# MasterSheet.net
KiCad netlist of a schematic drawn in Altium Designer
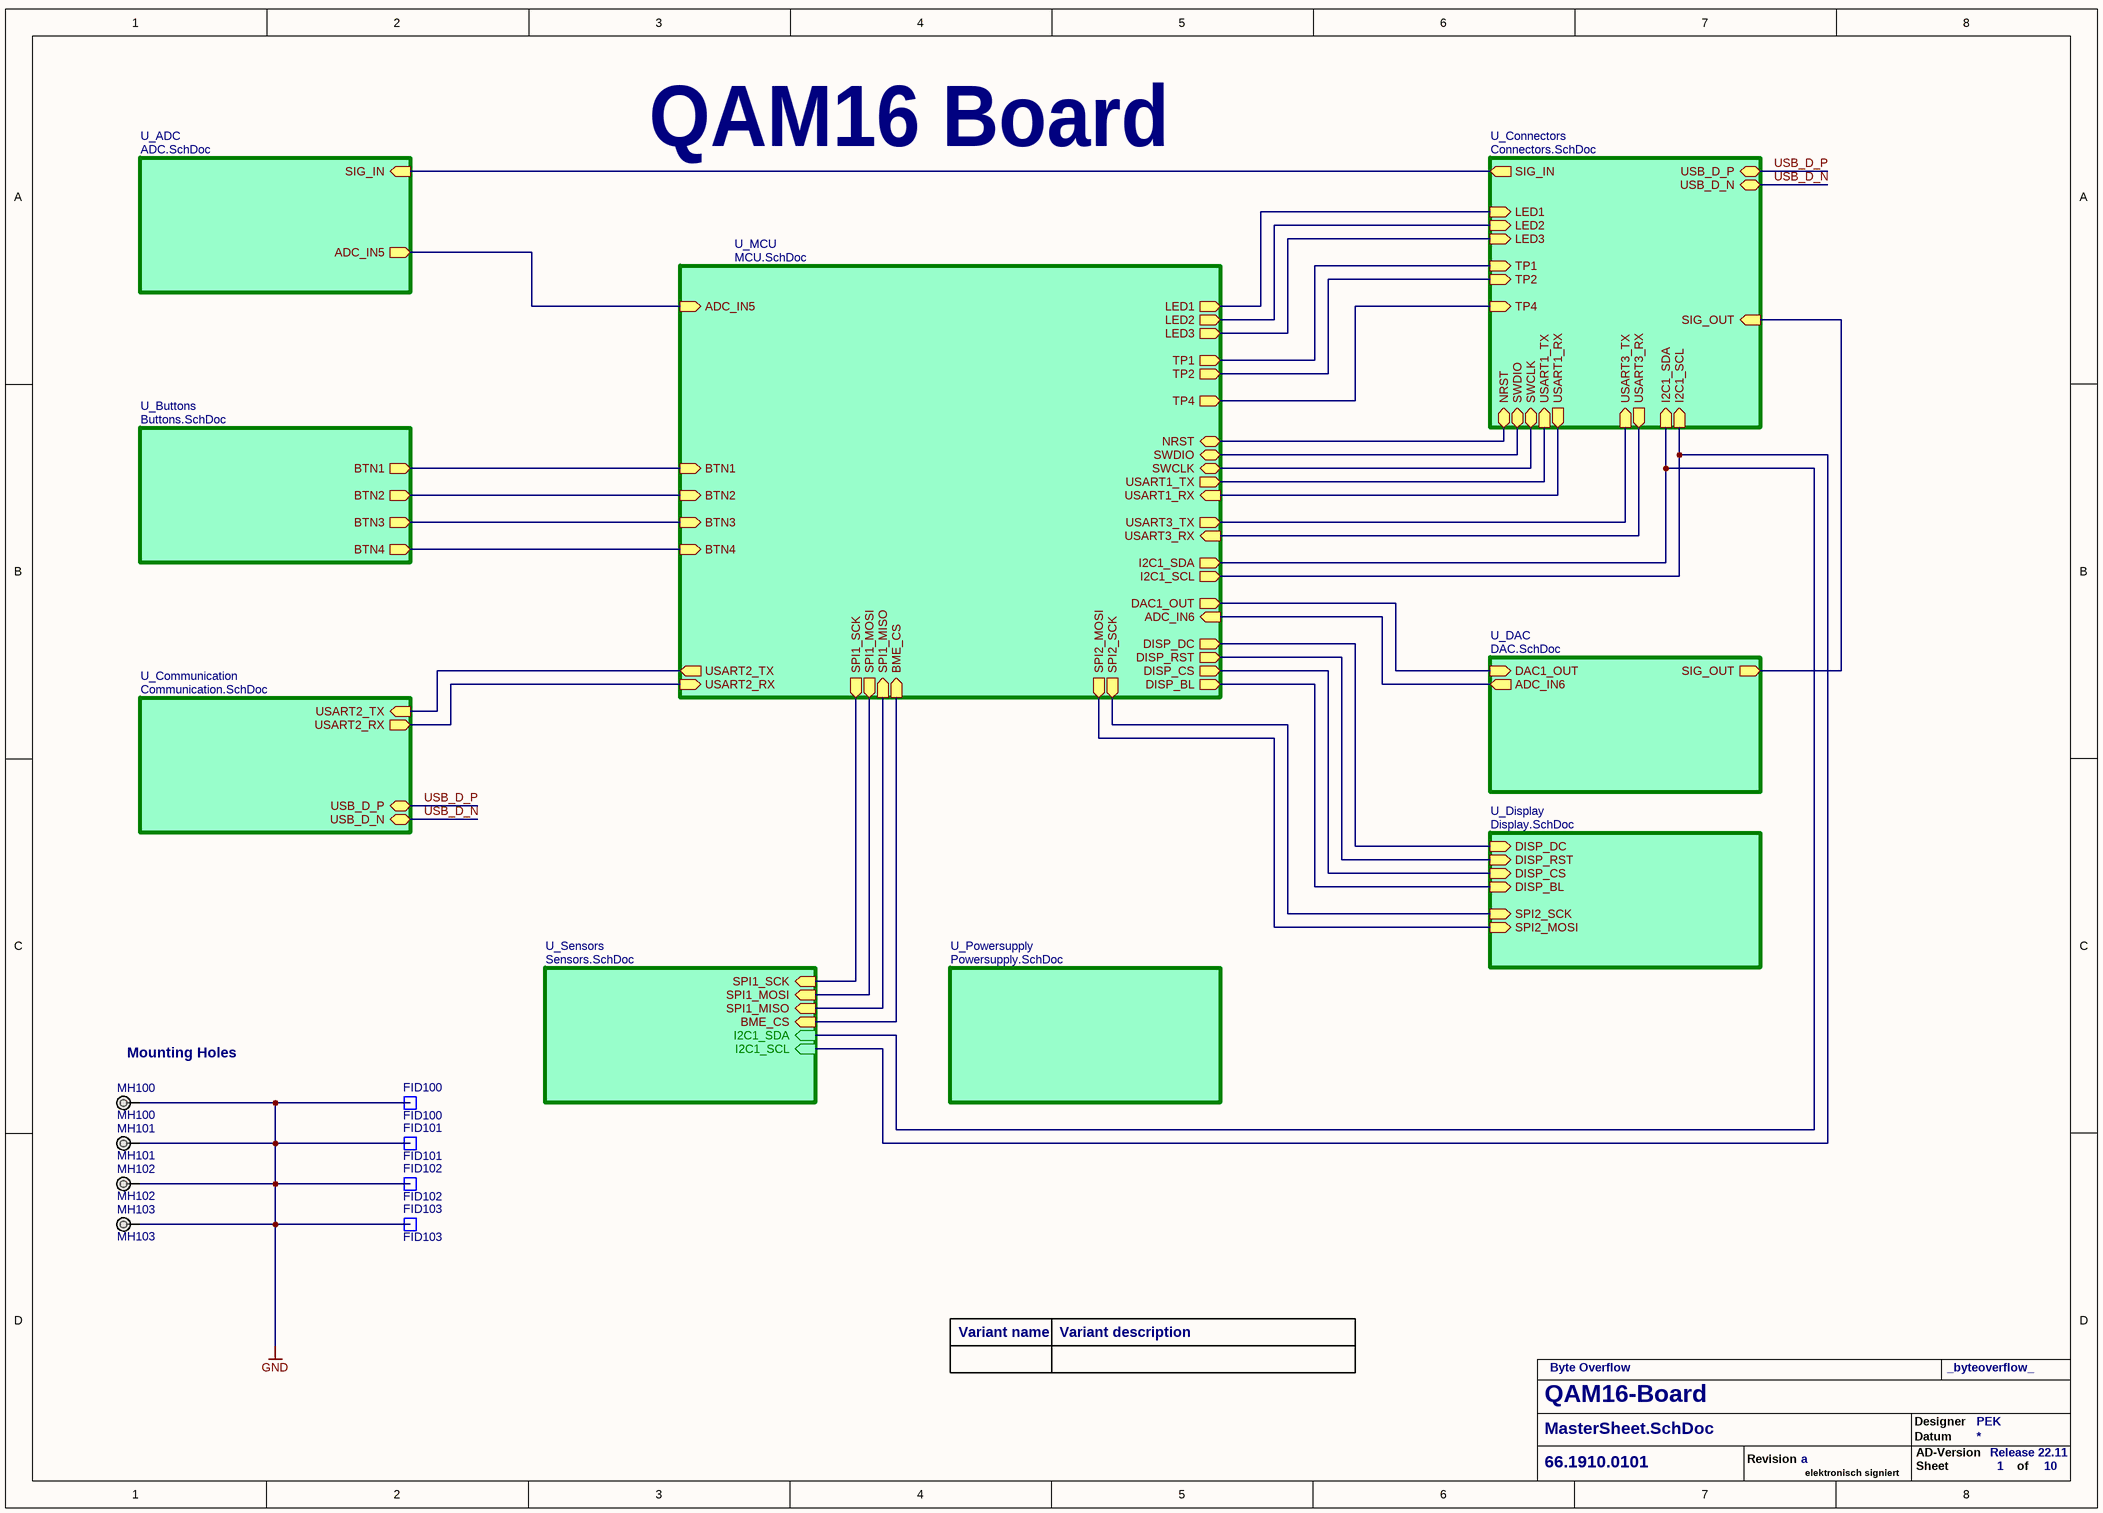
[diagram p0: MasterSheet.SchDoc]

(export (version "E")
  (design (tool "Eeschema 10.0.6"))
  (components
    (comp (ref "FID100")
      (value "FIDUCIAL-2")
      (footprint "FIDUCIAL_2")
      (description "FIDUCIAL")
      (libsource (lib "Database_Libs1") (part "FIDUCIAL"))
    )
    (comp (ref "FID101")
      (value "FIDUCIAL-2")
      (footprint "FIDUCIAL_2")
      (description "FIDUCIAL")
      (libsource (lib "Database_Libs1") (part "FIDUCIAL"))
    )
    (comp (ref "FID102")
      (value "FIDUCIAL-2")
      (footprint "FIDUCIAL_2")
      (description "FIDUCIAL")
      (libsource (lib "Database_Libs1") (part "FIDUCIAL"))
    )
    (comp (ref "FID103")
      (value "FIDUCIAL-2")
      (footprint "FIDUCIAL_2")
      (description "FIDUCIAL")
      (libsource (lib "Database_Libs1") (part "FIDUCIAL"))
    )
    (comp (ref "MH100")
      (value "MH_M3_RND_2")
      (footprint "MH_M3_RND_2")
      (description "PCB hole")
      (libsource (lib "Database_Libs1") (part "MH_RND"))
    )
    (comp (ref "MH101")
      (value "MH_M3_RND_2")
      (footprint "MH_M3_RND_2")
      (description "PCB hole")
      (libsource (lib "Database_Libs1") (part "MH_RND"))
    )
    (comp (ref "MH102")
      (value "MH_M3_RND_2")
      (footprint "MH_M3_RND_2")
      (description "PCB hole")
      (libsource (lib "Database_Libs1") (part "MH_RND"))
    )
    (comp (ref "MH103")
      (value "MH_M3_RND_2")
      (footprint "MH_M3_RND_2")
      (description "PCB hole")
      (libsource (lib "Database_Libs1") (part "MH_RND"))
    )
  )
  (nets
    (net (code "39") (name "GND") (class "Default")
      (node (ref "FID100") (pin "1") (pintype "passive"))
      (node (ref "FID101") (pin "1") (pintype "passive"))
      (node (ref "FID102") (pin "1") (pintype "passive"))
      (node (ref "FID103") (pin "1") (pintype "passive"))
      (node (ref "MH100") (pin "1") (pintype "passive"))
      (node (ref "MH101") (pin "1") (pintype "passive"))
      (node (ref "MH102") (pin "1") (pintype "passive"))
      (node (ref "MH103") (pin "1") (pintype "passive"))
    )
  )
)
